# 214_oled_Rev020000.net
KiCad netlist of a schematic drawn in EAGLE
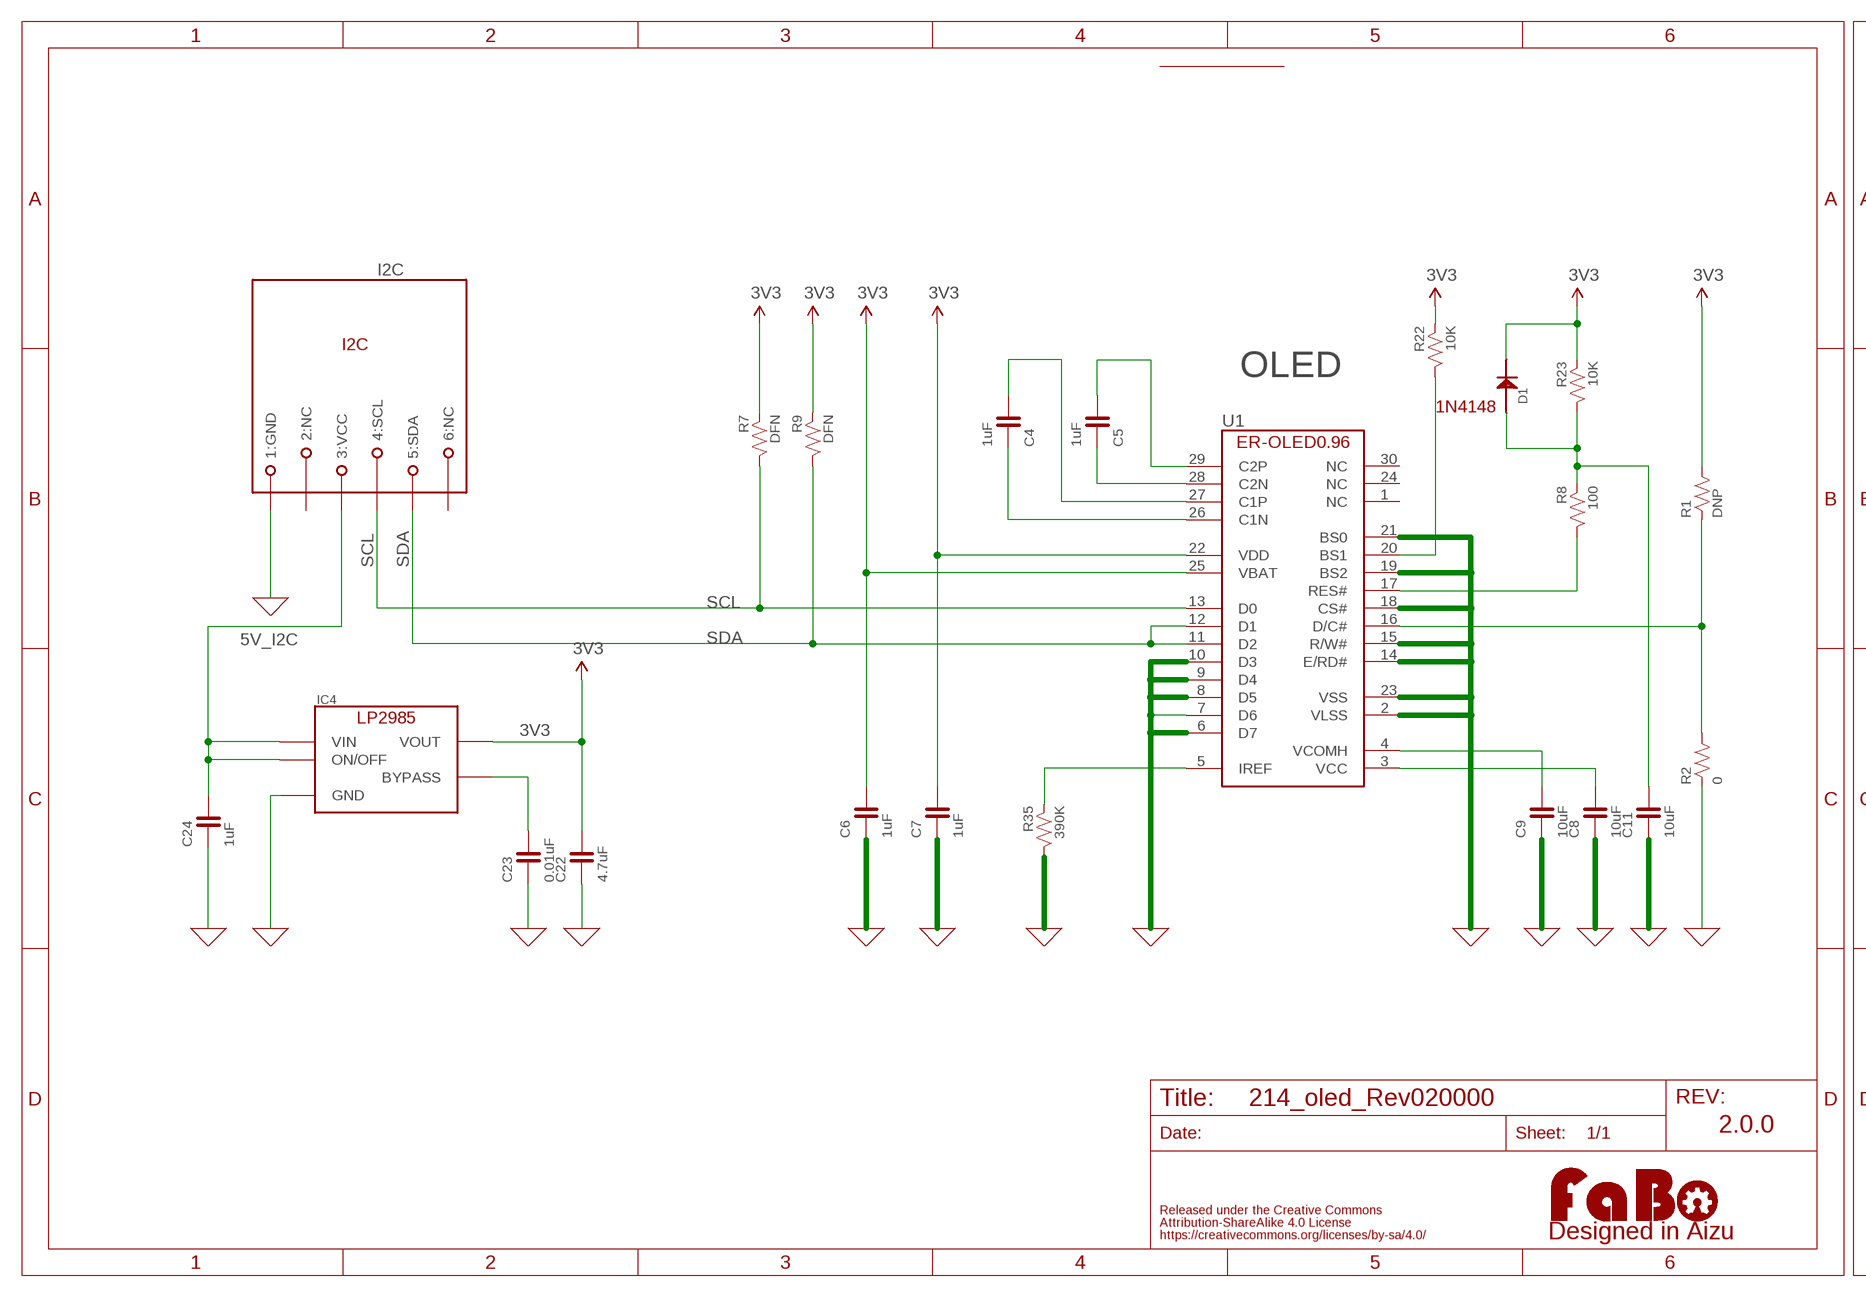
[diagram p0: schematic, sheet 1, part 1 of 2]
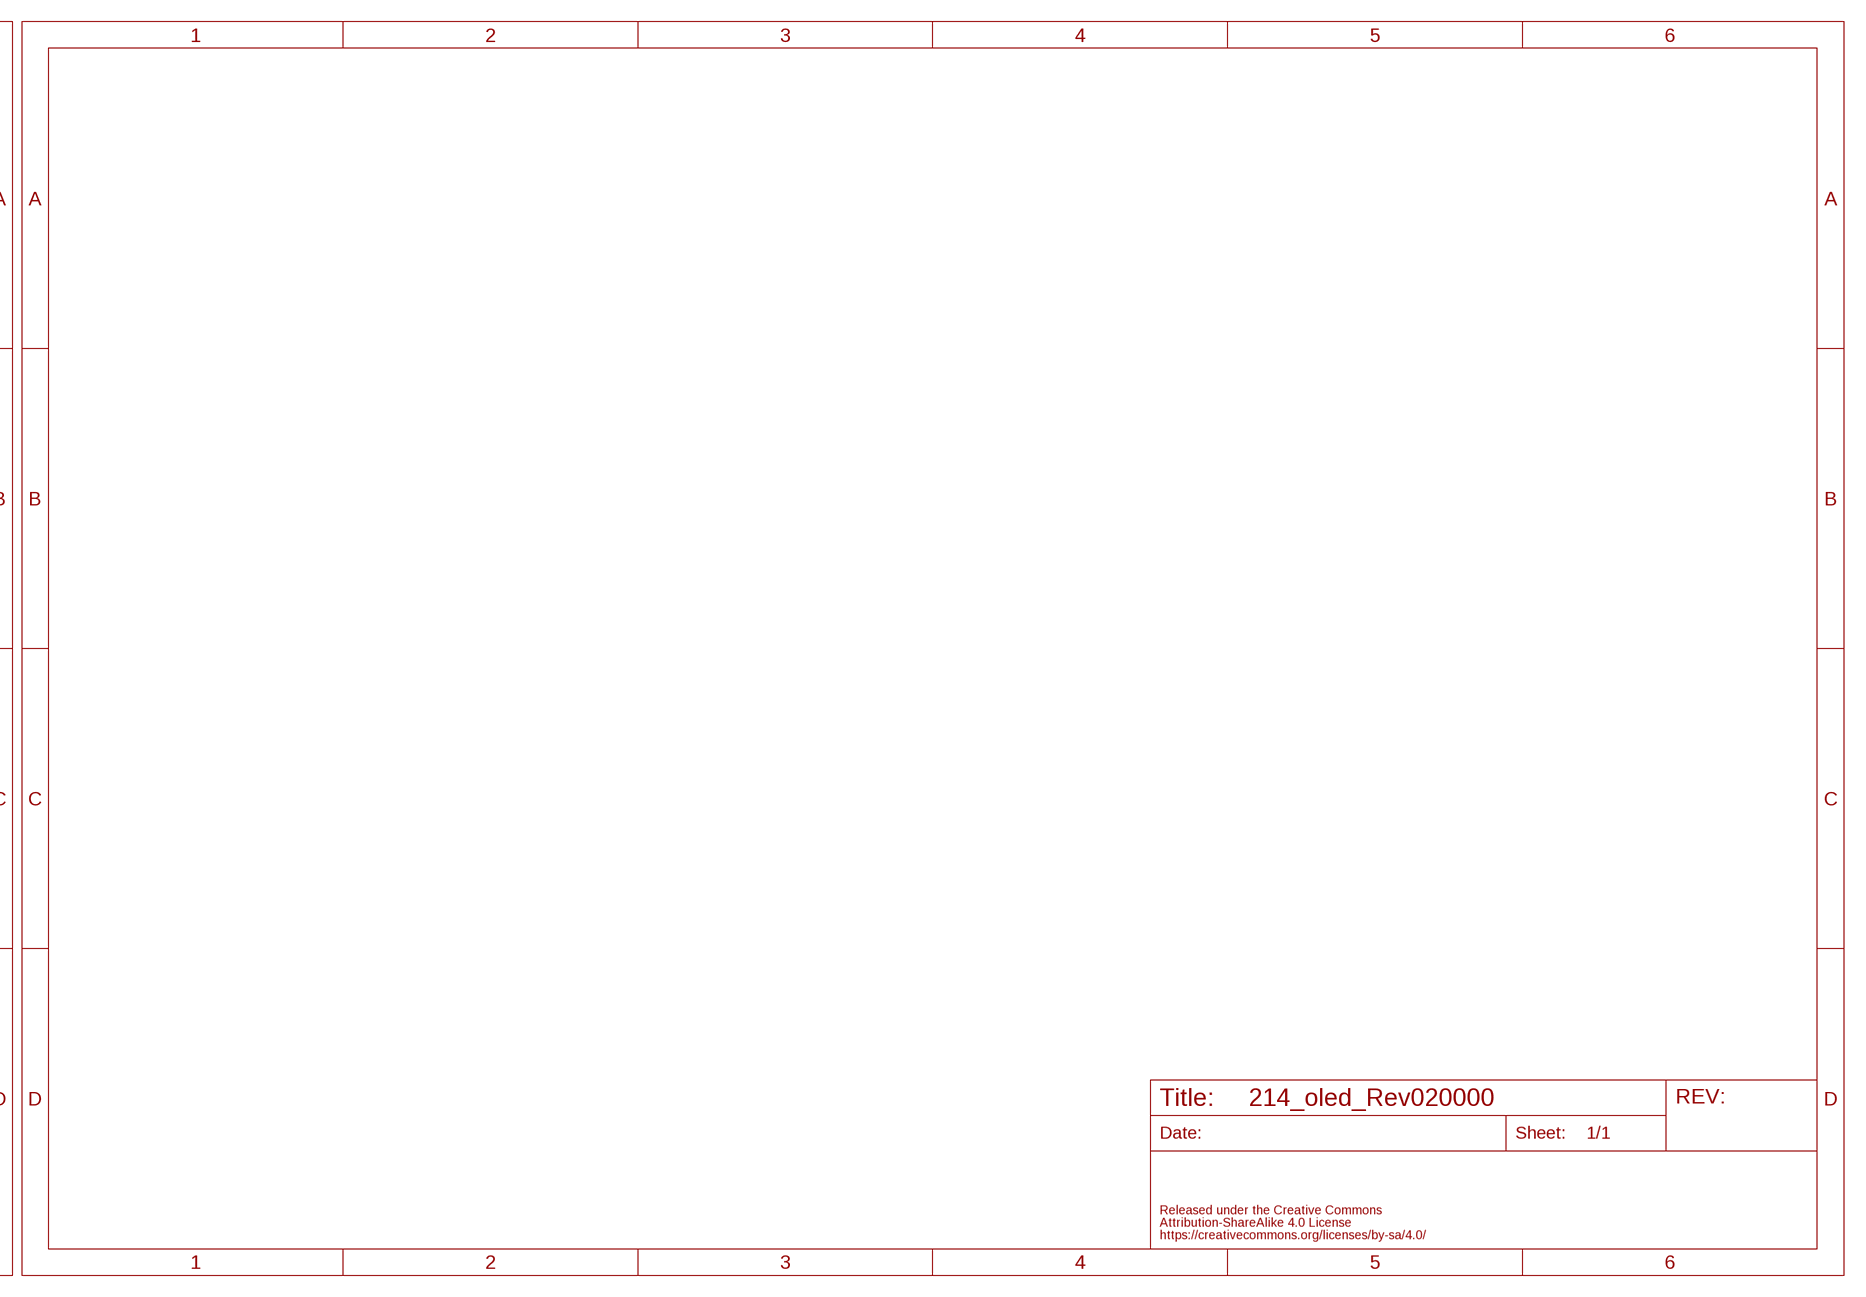
[diagram p1: schematic, sheet 1, part 2 of 2]

(export (version "E")
  (design (tool "Eeschema 10.0.6"))
  (components
    (comp (ref "C4")
      (value "1uF")
      (footprint "eagle-import:0603")
      (libsource (lib "eagle-import") (part "CAPACITOR-0603"))
    )
    (comp (ref "C5")
      (value "1uF")
      (footprint "eagle-import:0603")
      (libsource (lib "eagle-import") (part "CAPACITOR-0603"))
    )
    (comp (ref "C6")
      (value "1uF")
      (footprint "eagle-import:0603")
      (libsource (lib "eagle-import") (part "CAPACITOR-0603"))
    )
    (comp (ref "C7")
      (value "1uF")
      (footprint "eagle-import:0603")
      (libsource (lib "eagle-import") (part "CAPACITOR-0603"))
    )
    (comp (ref "C8")
      (value "10uF")
      (footprint "eagle-import:0603")
      (libsource (lib "eagle-import") (part "CAPACITOR-0603"))
    )
    (comp (ref "C9")
      (value "10uF")
      (footprint "eagle-import:0603")
      (libsource (lib "eagle-import") (part "CAPACITOR-0603"))
    )
    (comp (ref "C11")
      (value "10uF")
      (footprint "eagle-import:0603")
      (libsource (lib "eagle-import") (part "CAPACITOR-0603"))
    )
    (comp (ref "C22")
      (value "4.7uF")
      (footprint "eagle-import:0603")
      (libsource (lib "eagle-import") (part "CAPACITOR-0603"))
    )
    (comp (ref "C23")
      (value "0.01uF")
      (footprint "eagle-import:0603")
      (libsource (lib "eagle-import") (part "CAPACITOR-0603"))
    )
    (comp (ref "C24")
      (value "1uF")
      (footprint "eagle-import:0603")
      (libsource (lib "eagle-import") (part "CAPACITOR-0603"))
    )
    (comp (ref "D1")
      (value "1N4148")
      (footprint "eagle-import:1N4148W")
      (libsource (lib "eagle-import") (part "1N4148"))
    )
    (comp (ref "I2C")
      (value "MODULAR-JACK-6P-RJ11_I2C")
      (footprint "eagle-import:7002-6PXC-X")
      (libsource (lib "eagle-import") (part "MODULAR-JACK-6P-RJ11_I2C"))
    )
    (comp (ref "IC4")
      (value "LP2985-33DBV")
      (footprint "eagle-import:SOT-23-5")
      (libsource (lib "eagle-import") (part "LP2985-33DBV"))
    )
    (comp (ref "LOGO1")
      (value "LOGO_FABO-M_BOTTOM")
      (footprint "eagle-import:LOGO_FABO_M_BOTTOM")
      (libsource (lib "eagle-import") (part "LOGO_FABO-M_BOTTOM"))
    )
    (comp (ref "R1")
      (value "DNP")
      (footprint "eagle-import:0805")
      (fields (field (name "SPICEPREFIX") "R"))
      (libsource (lib "eagle-import") (part "RESISTOR-0805"))
    )
    (comp (ref "R2")
      (value "0")
      (footprint "eagle-import:0805")
      (libsource (lib "eagle-import") (part "RESISTOR-0805"))
    )
    (comp (ref "R7")
      (value "DFN")
      (footprint "eagle-import:0603")
      (libsource (lib "eagle-import") (part "RESISTOR-0603"))
    )
    (comp (ref "R8")
      (value "100")
      (footprint "eagle-import:0603")
      (libsource (lib "eagle-import") (part "RESISTOR-0603"))
    )
    (comp (ref "R9")
      (value "DFN")
      (footprint "eagle-import:0603")
      (libsource (lib "eagle-import") (part "RESISTOR-0603"))
    )
    (comp (ref "R22")
      (value "10K")
      (footprint "eagle-import:0603")
      (libsource (lib "eagle-import") (part "RESISTOR-0603"))
    )
    (comp (ref "R23")
      (value "10K")
      (footprint "eagle-import:0603")
      (libsource (lib "eagle-import") (part "RESISTOR-0603"))
    )
    (comp (ref "R35")
      (value "390K")
      (footprint "eagle-import:0603")
      (libsource (lib "eagle-import") (part "RESISTOR-0603"))
    )
    (comp (ref "U1")
      (value "ER-OLED0.96-1ER-CON30HT-1")
      (footprint "eagle-import:ER-CON30HT-1")
      (libsource (lib "eagle-import") (part "ER-OLED0.96-1ER-CON30HT-1"))
    )
  )
  (nets
    (net (code "1") (name "/5V_I2C") (class "Default")
      (node (ref "C24") (pin "2") (pinfunction "2_2") (pintype "passive"))
      (node (ref "I2C") (pin "3") (pinfunction "3:VCC_3") (pintype "power_in"))
      (node (ref "IC4") (pin "1") (pinfunction "VIN_1") (pintype "input"))
      (node (ref "IC4") (pin "3") (pinfunction "ON/OFF_3") (pintype "input"))
    )
    (net (code "2") (name "/SCL") (class "Default")
      (node (ref "I2C") (pin "4") (pinfunction "4:SCL_4") (pintype "open_collector"))
      (node (ref "R7") (pin "2") (pinfunction "2_2") (pintype "bidirectional"))
      (node (ref "U1") (pin "13") (pinfunction "D0_13") (pintype "bidirectional"))
    )
    (net (code "3") (name "/SDA") (class "Default")
      (node (ref "I2C") (pin "5") (pinfunction "5:SDA_5") (pintype "open_collector"))
      (node (ref "R9") (pin "2") (pinfunction "2_2") (pintype "bidirectional"))
      (node (ref "U1") (pin "11") (pinfunction "D2_11") (pintype "bidirectional"))
      (node (ref "U1") (pin "12") (pinfunction "D1_12") (pintype "bidirectional"))
    )
    (net (code "4") (name "3V3") (class "Default")
      (node (ref "C22") (pin "2") (pinfunction "2_2") (pintype "passive"))
      (node (ref "C6") (pin "2") (pinfunction "2_2") (pintype "passive"))
      (node (ref "C7") (pin "2") (pinfunction "2_2") (pintype "passive"))
      (node (ref "D1") (pin "CATHODE") (pinfunction "CATHODE_CATHODE") (pintype "bidirectional"))
      (node (ref "IC4") (pin "5") (pinfunction "VOUT_5") (pintype "output"))
      (node (ref "R1") (pin "2") (pinfunction "2_2") (pintype "bidirectional"))
      (node (ref "R22") (pin "1") (pinfunction "1_1") (pintype "bidirectional"))
      (node (ref "R23") (pin "1") (pinfunction "1_1") (pintype "bidirectional"))
      (node (ref "R7") (pin "1") (pinfunction "1_1") (pintype "bidirectional"))
      (node (ref "R9") (pin "1") (pinfunction "1_1") (pintype "bidirectional"))
      (node (ref "U1") (pin "22") (pinfunction "VDD_22") (pintype "bidirectional"))
      (node (ref "U1") (pin "25") (pinfunction "VBAT_25") (pintype "bidirectional"))
    )
    (net (code "5") (name "GND") (class "Default")
      (node (ref "C11") (pin "1") (pinfunction "1_1") (pintype "passive"))
      (node (ref "C22") (pin "1") (pinfunction "1_1") (pintype "passive"))
      (node (ref "C23") (pin "1") (pinfunction "1_1") (pintype "passive"))
      (node (ref "C24") (pin "1") (pinfunction "1_1") (pintype "passive"))
      (node (ref "C6") (pin "1") (pinfunction "1_1") (pintype "passive"))
      (node (ref "C7") (pin "1") (pinfunction "1_1") (pintype "passive"))
      (node (ref "C8") (pin "1") (pinfunction "1_1") (pintype "passive"))
      (node (ref "C9") (pin "1") (pinfunction "1_1") (pintype "passive"))
      (node (ref "I2C") (pin "1") (pinfunction "1:GND_1") (pintype "power_in"))
      (node (ref "IC4") (pin "2") (pinfunction "GND_2") (pintype "power_in"))
      (node (ref "R2") (pin "1") (pinfunction "1_1") (pintype "bidirectional"))
      (node (ref "R35") (pin "2") (pinfunction "2_2") (pintype "bidirectional"))
      (node (ref "U1") (pin "10") (pinfunction "D3_10") (pintype "bidirectional"))
      (node (ref "U1") (pin "14") (pinfunction "E/RD#_14") (pintype "bidirectional"))
      (node (ref "U1") (pin "15") (pinfunction "R/W#_15") (pintype "bidirectional"))
      (node (ref "U1") (pin "18") (pinfunction "CS#_18") (pintype "bidirectional"))
      (node (ref "U1") (pin "19") (pinfunction "BS2_19") (pintype "bidirectional"))
      (node (ref "U1") (pin "2") (pinfunction "VLSS_2") (pintype "bidirectional"))
      (node (ref "U1") (pin "21") (pinfunction "BS0_21") (pintype "bidirectional"))
      (node (ref "U1") (pin "23") (pinfunction "VSS_23") (pintype "bidirectional"))
      (node (ref "U1") (pin "6") (pinfunction "D7_6") (pintype "bidirectional"))
      (node (ref "U1") (pin "7") (pinfunction "D6_7") (pintype "bidirectional"))
      (node (ref "U1") (pin "8") (pinfunction "D5_8") (pintype "bidirectional"))
      (node (ref "U1") (pin "9") (pinfunction "D4_9") (pintype "bidirectional"))
    )
    (net (code "6") (name "Net-(C11-Pad2)") (class "Default")
      (node (ref "C11") (pin "2") (pinfunction "2_2") (pintype "passive"))
      (node (ref "D1") (pin "ANODE") (pinfunction "ANODE_ANODE") (pintype "bidirectional"))
      (node (ref "R23") (pin "2") (pinfunction "2_2") (pintype "bidirectional"))
      (node (ref "R8") (pin "1") (pinfunction "1_1") (pintype "bidirectional"))
    )
    (net (code "7") (name "Net-(IC4-BYPASS)") (class "Default")
      (node (ref "C23") (pin "2") (pinfunction "2_2") (pintype "passive"))
      (node (ref "IC4") (pin "4") (pinfunction "BYPASS_4") (pintype "bidirectional"))
    )
    (net (code "8") (name "Net-(U1-BS1)") (class "Default")
      (node (ref "R22") (pin "2") (pinfunction "2_2") (pintype "bidirectional"))
      (node (ref "U1") (pin "20") (pinfunction "BS1_20") (pintype "bidirectional"))
    )
    (net (code "9") (name "Net-(U1-C1N)") (class "Default")
      (node (ref "C4") (pin "1") (pinfunction "1_1") (pintype "passive"))
      (node (ref "U1") (pin "26") (pinfunction "C1N_26") (pintype "bidirectional"))
    )
    (net (code "10") (name "Net-(U1-C1P)") (class "Default")
      (node (ref "C4") (pin "2") (pinfunction "2_2") (pintype "passive"))
      (node (ref "U1") (pin "27") (pinfunction "C1P_27") (pintype "bidirectional"))
    )
    (net (code "11") (name "Net-(U1-C2N)") (class "Default")
      (node (ref "C5") (pin "1") (pinfunction "1_1") (pintype "passive"))
      (node (ref "U1") (pin "28") (pinfunction "C2N_28") (pintype "bidirectional"))
    )
    (net (code "12") (name "Net-(U1-C2P)") (class "Default")
      (node (ref "C5") (pin "2") (pinfunction "2_2") (pintype "passive"))
      (node (ref "U1") (pin "29") (pinfunction "C2P_29") (pintype "bidirectional"))
    )
    (net (code "13") (name "Net-(U1-D{slash}C#)") (class "Default")
      (node (ref "R1") (pin "1") (pinfunction "1_1") (pintype "bidirectional"))
      (node (ref "R2") (pin "2") (pinfunction "2_2") (pintype "bidirectional"))
      (node (ref "U1") (pin "16") (pinfunction "D/C#_16") (pintype "bidirectional"))
    )
    (net (code "14") (name "Net-(U1-IREF)") (class "Default")
      (node (ref "R35") (pin "1") (pinfunction "1_1") (pintype "bidirectional"))
      (node (ref "U1") (pin "5") (pinfunction "IREF_5") (pintype "bidirectional"))
    )
    (net (code "15") (name "Net-(U1-RES#)") (class "Default")
      (node (ref "R8") (pin "2") (pinfunction "2_2") (pintype "bidirectional"))
      (node (ref "U1") (pin "17") (pinfunction "RES#_17") (pintype "bidirectional"))
    )
    (net (code "16") (name "Net-(U1-VCC)") (class "Default")
      (node (ref "C8") (pin "2") (pinfunction "2_2") (pintype "passive"))
      (node (ref "U1") (pin "3") (pinfunction "VCC_3") (pintype "bidirectional"))
    )
    (net (code "17") (name "Net-(U1-VCOMH)") (class "Default")
      (node (ref "C9") (pin "2") (pinfunction "2_2") (pintype "passive"))
      (node (ref "U1") (pin "4") (pinfunction "VCOMH_4") (pintype "bidirectional"))
    )
    (net (code "18") (name "unconnected-(I2C-2:NC-Pad2)") (class "Default")
      (node (ref "I2C") (pin "2") (pinfunction "2:NC_2") (pintype "no_connect"))
    )
    (net (code "19") (name "unconnected-(I2C-6:NC-Pad6)") (class "Default")
      (node (ref "I2C") (pin "6") (pinfunction "6:NC_6") (pintype "no_connect"))
    )
    (net (code "20") (name "unconnected-(U1-NC-Pad1)") (class "Default")
      (node (ref "U1") (pin "1") (pinfunction "NC_1") (pintype "bidirectional"))
    )
    (net (code "21") (name "unconnected-(U1-NC-Pad24)") (class "Default")
      (node (ref "U1") (pin "24") (pinfunction "NC_24") (pintype "bidirectional"))
    )
    (net (code "22") (name "unconnected-(U1-NC-Pad30)") (class "Default")
      (node (ref "U1") (pin "30") (pinfunction "NC_30") (pintype "bidirectional"))
    )
  )
)
